# openTPM-v35.net
KiCad netlist of a schematic drawn in EAGLE
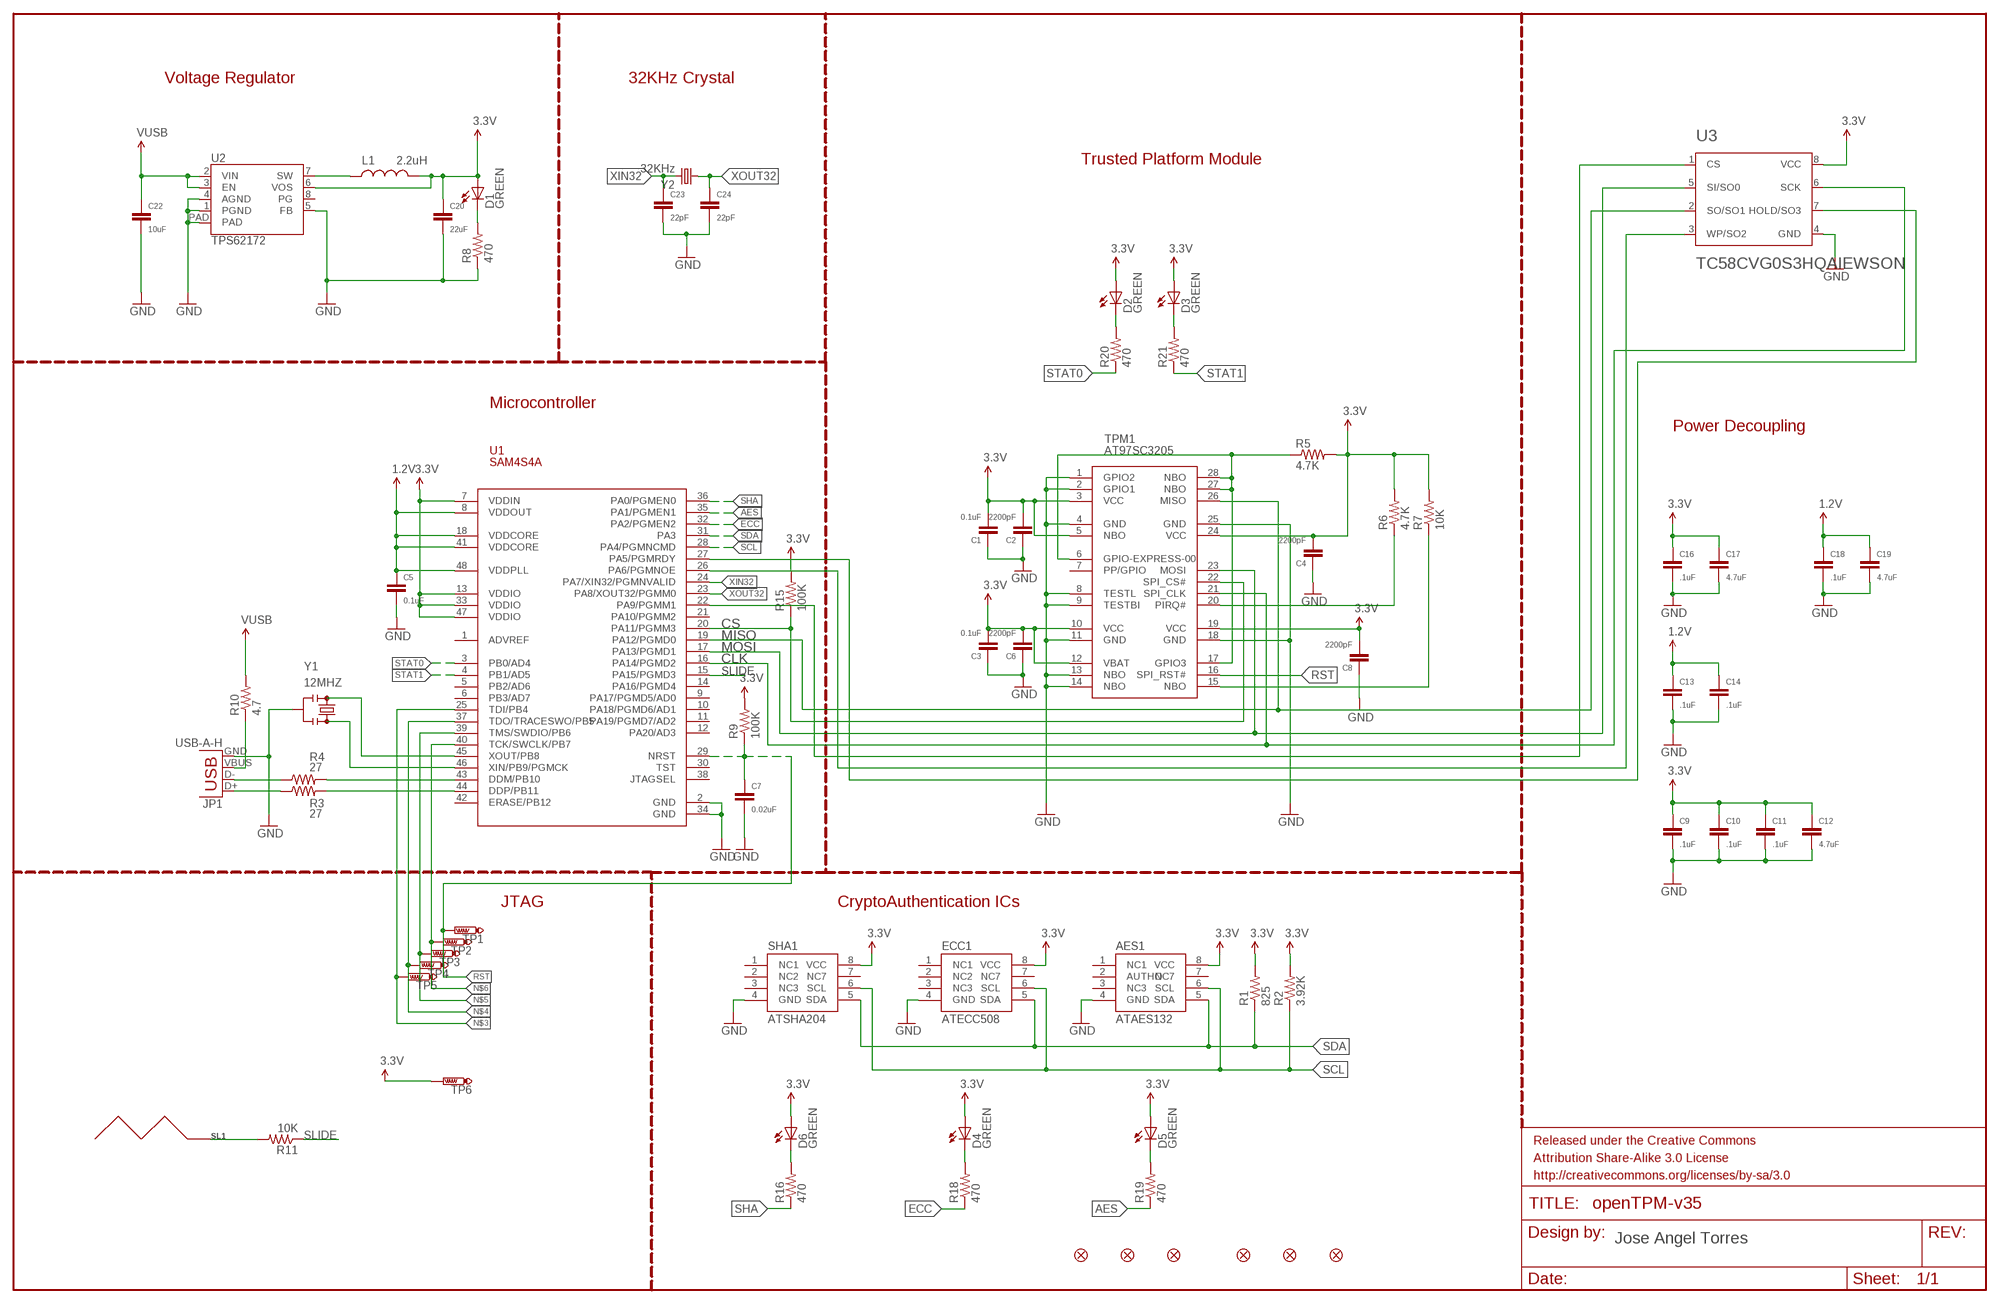
[diagram p0: schematic, sheet 1]

(export (version "E")
  (design (tool "Eeschema 10.0.6"))
  (components
    (comp (ref "AES1")
      (value "ATAES132")
      (footprint "eagle-import:CRYPTOTRONIX_SOIC8")
      (libsource (lib "eagle-import") (part "CRYPTOTRONIX_ATAES132"))
    )
    (comp (ref "C1")
      (value "0.1uF")
      (footprint "eagle-import:0402")
      (libsource (lib "eagle-import") (part "CAPACITOR.0402"))
    )
    (comp (ref "C2")
      (value "2200pF")
      (footprint "eagle-import:0402")
      (libsource (lib "eagle-import") (part "CAPACITOR.0402"))
    )
    (comp (ref "C3")
      (value "0.1uF")
      (footprint "eagle-import:0402")
      (libsource (lib "eagle-import") (part "CAPACITOR.0402"))
    )
    (comp (ref "C4")
      (value "2200pF")
      (footprint "eagle-import:0402")
      (libsource (lib "eagle-import") (part "CAPACITOR.0402"))
    )
    (comp (ref "C5")
      (value "0.1uF")
      (footprint "eagle-import:0402")
      (libsource (lib "eagle-import") (part "CAPACITOR.0402"))
    )
    (comp (ref "C6")
      (value "2200pF")
      (footprint "eagle-import:0402")
      (libsource (lib "eagle-import") (part "CAPACITOR.0402"))
    )
    (comp (ref "C7")
      (value "0.02uF")
      (footprint "eagle-import:0402")
      (libsource (lib "eagle-import") (part "CAPACITOR.0402"))
    )
    (comp (ref "C8")
      (value "2200pF")
      (footprint "eagle-import:0402")
      (libsource (lib "eagle-import") (part "CAPACITOR.0402"))
    )
    (comp (ref "C9")
      (value ".1uF")
      (footprint "eagle-import:0402")
      (libsource (lib "eagle-import") (part "CAPACITOR.0402"))
    )
    (comp (ref "C10")
      (value ".1uF")
      (footprint "eagle-import:0402")
      (libsource (lib "eagle-import") (part "CAPACITOR.0402"))
    )
    (comp (ref "C11")
      (value ".1uF")
      (footprint "eagle-import:0402")
      (libsource (lib "eagle-import") (part "CAPACITOR.0402"))
    )
    (comp (ref "C12")
      (value "4.7uF")
      (footprint "eagle-import:0402")
      (libsource (lib "eagle-import") (part "CAPACITOR.0402"))
    )
    (comp (ref "C13")
      (value ".1uF")
      (footprint "eagle-import:0402")
      (libsource (lib "eagle-import") (part "CAPACITOR.0402"))
    )
    (comp (ref "C14")
      (value ".1uF")
      (footprint "eagle-import:0402")
      (libsource (lib "eagle-import") (part "CAPACITOR.0402"))
    )
    (comp (ref "C16")
      (value ".1uF")
      (footprint "eagle-import:0402")
      (libsource (lib "eagle-import") (part "CAPACITOR.0402"))
    )
    (comp (ref "C17")
      (value "4.7uF")
      (footprint "eagle-import:0402")
      (libsource (lib "eagle-import") (part "CAPACITOR.0402"))
    )
    (comp (ref "C18")
      (value ".1uF")
      (footprint "eagle-import:0402")
      (libsource (lib "eagle-import") (part "CAPACITOR.0402"))
    )
    (comp (ref "C19")
      (value "4.7uF")
      (footprint "eagle-import:0402")
      (libsource (lib "eagle-import") (part "CAPACITOR.0402"))
    )
    (comp (ref "C20")
      (value "22uF")
      (footprint "eagle-import:0603")
      (libsource (lib "eagle-import") (part "CAPACITOR.0603"))
    )
    (comp (ref "C22")
      (value "10uF")
      (footprint "eagle-import:0402")
      (libsource (lib "eagle-import") (part "CAPACITOR.0402"))
    )
    (comp (ref "C23")
      (value "22pF")
      (footprint "eagle-import:0402")
      (libsource (lib "eagle-import") (part "CAPACITOR.0402"))
    )
    (comp (ref "C24")
      (value "22pF")
      (footprint "eagle-import:0402")
      (libsource (lib "eagle-import") (part "CAPACITOR.0402"))
    )
    (comp (ref "D1")
      (value "GREEN")
      (footprint "eagle-import:SPARKFUN-LED_LED-0603")
      (libsource (lib "eagle-import") (part "SPARKFUN-LED_LED-GREEN0603"))
    )
    (comp (ref "D2")
      (value "GREEN")
      (footprint "eagle-import:SPARKFUN-LED_LED-0603")
      (libsource (lib "eagle-import") (part "SPARKFUN-LED_LED-GREEN0603"))
    )
    (comp (ref "D3")
      (value "GREEN")
      (footprint "eagle-import:SPARKFUN-LED_LED-0603")
      (libsource (lib "eagle-import") (part "SPARKFUN-LED_LED-GREEN0603"))
    )
    (comp (ref "D4")
      (value "GREEN")
      (footprint "eagle-import:SPARKFUN-LED_LED-0603")
      (libsource (lib "eagle-import") (part "SPARKFUN-LED_LED-GREEN0603"))
    )
    (comp (ref "D5")
      (value "GREEN")
      (footprint "eagle-import:SPARKFUN-LED_LED-0603")
      (libsource (lib "eagle-import") (part "SPARKFUN-LED_LED-GREEN0603"))
    )
    (comp (ref "D6")
      (value "GREEN")
      (footprint "eagle-import:SPARKFUN-LED_LED-0603")
      (libsource (lib "eagle-import") (part "SPARKFUN-LED_LED-GREEN0603"))
    )
    (comp (ref "ECC1")
      (value "ATECC508")
      (footprint "eagle-import:CRYPTOTRONIX_SOIC8")
      (libsource (lib "eagle-import") (part "ATECC508"))
    )
    (comp (ref "FID1")
      (value "SPARKFUN-AESTHETICS_FIDUCIAL1X2")
      (footprint "eagle-import:SPARKFUN-AESTHETICS_FIDUCIAL-1X2")
      (libsource (lib "eagle-import") (part "SPARKFUN-AESTHETICS_FIDUCIAL1X2"))
    )
    (comp (ref "FID2")
      (value "SPARKFUN-AESTHETICS_FIDUCIAL1X2")
      (footprint "eagle-import:SPARKFUN-AESTHETICS_FIDUCIAL-1X2")
      (libsource (lib "eagle-import") (part "SPARKFUN-AESTHETICS_FIDUCIAL1X2"))
    )
    (comp (ref "FID3")
      (value "SPARKFUN-AESTHETICS_FIDUCIAL1X2")
      (footprint "eagle-import:SPARKFUN-AESTHETICS_FIDUCIAL-1X2")
      (libsource (lib "eagle-import") (part "SPARKFUN-AESTHETICS_FIDUCIAL1X2"))
    )
    (comp (ref "FID4")
      (value "SPARKFUN-AESTHETICS_FIDUCIAL1X2")
      (footprint "eagle-import:SPARKFUN-AESTHETICS_FIDUCIAL-1X2")
      (libsource (lib "eagle-import") (part "SPARKFUN-AESTHETICS_FIDUCIAL1X2"))
    )
    (comp (ref "FID5")
      (value "SPARKFUN-AESTHETICS_FIDUCIAL1X2")
      (footprint "eagle-import:SPARKFUN-AESTHETICS_FIDUCIAL-1X2")
      (libsource (lib "eagle-import") (part "SPARKFUN-AESTHETICS_FIDUCIAL1X2"))
    )
    (comp (ref "FID6")
      (value "SPARKFUN-AESTHETICS_FIDUCIAL1X2")
      (footprint "eagle-import:SPARKFUN-AESTHETICS_FIDUCIAL-1X2")
      (libsource (lib "eagle-import") (part "SPARKFUN-AESTHETICS_FIDUCIAL1X2"))
    )
    (comp (ref "JP1")
      (value "USB-A-H")
      (footprint "eagle-import:USB-A-H")
      (libsource (lib "eagle-import") (part "USB-A-H"))
    )
    (comp (ref "L1")
      (value "2.2uH")
      (footprint "eagle-import:C0402")
      (libsource (lib "eagle-import") (part "INDUCTOR0402"))
    )
    (comp (ref "R1")
      (value "825")
      (footprint "eagle-import:0402")
      (libsource (lib "eagle-import") (part "RESISTOR.0402"))
    )
    (comp (ref "R2")
      (value "3.92K")
      (footprint "eagle-import:0402")
      (libsource (lib "eagle-import") (part "RESISTOR.0402"))
    )
    (comp (ref "R3")
      (value "27")
      (footprint "eagle-import:0402")
      (libsource (lib "eagle-import") (part "RESISTOR.0402"))
    )
    (comp (ref "R4")
      (value "27")
      (footprint "eagle-import:0402")
      (libsource (lib "eagle-import") (part "RESISTOR.0402"))
    )
    (comp (ref "R5")
      (value "4.7K")
      (footprint "eagle-import:0402")
      (libsource (lib "eagle-import") (part "RESISTOR.0402"))
    )
    (comp (ref "R6")
      (value "4.7K")
      (footprint "eagle-import:0402")
      (libsource (lib "eagle-import") (part "RESISTOR.0402"))
    )
    (comp (ref "R7")
      (value "10K")
      (footprint "eagle-import:0402")
      (libsource (lib "eagle-import") (part "RESISTOR.0402"))
    )
    (comp (ref "R8")
      (value "470")
      (footprint "eagle-import:0402")
      (libsource (lib "eagle-import") (part "RESISTOR.0402"))
    )
    (comp (ref "R9")
      (value "100K")
      (footprint "eagle-import:0402")
      (libsource (lib "eagle-import") (part "RESISTOR.0402"))
    )
    (comp (ref "R10")
      (value "4.7")
      (footprint "eagle-import:0402")
      (libsource (lib "eagle-import") (part "RESISTOR.0402"))
    )
    (comp (ref "R11")
      (value "10K")
      (footprint "eagle-import:0402")
      (libsource (lib "eagle-import") (part "RESISTOR.0402"))
    )
    (comp (ref "R15")
      (value "100K")
      (footprint "eagle-import:0402")
      (libsource (lib "eagle-import") (part "RESISTOR.0402"))
    )
    (comp (ref "R16")
      (value "470")
      (footprint "eagle-import:0402")
      (libsource (lib "eagle-import") (part "RESISTOR.0402"))
    )
    (comp (ref "R18")
      (value "470")
      (footprint "eagle-import:0402")
      (libsource (lib "eagle-import") (part "RESISTOR.0402"))
    )
    (comp (ref "R19")
      (value "470")
      (footprint "eagle-import:0402")
      (libsource (lib "eagle-import") (part "RESISTOR.0402"))
    )
    (comp (ref "R20")
      (value "470")
      (footprint "eagle-import:0402")
      (libsource (lib "eagle-import") (part "RESISTOR.0402"))
    )
    (comp (ref "R21")
      (value "470")
      (footprint "eagle-import:0402")
      (libsource (lib "eagle-import") (part "RESISTOR.0402"))
    )
    (comp (ref "SHA1")
      (value "ATSHA204")
      (footprint "eagle-import:CRYPTOTRONIX_SOIC8")
      (libsource (lib "eagle-import") (part "CRYPTOTRONIX_ATSHA204"))
    )
    (comp (ref "SL1")
      (value "SLIDER_PASSIVE_1SEG")
      (footprint "eagle-import:SLIDER_PASSIVE_1SEG_12MM")
      (libsource (lib "eagle-import") (part "SLIDER_PASSIVE_1SEG"))
    )
    (comp (ref "TP1")
      (value "PTR1B1,27")
      (footprint "eagle-import:B1,27")
      (libsource (lib "eagle-import") (part "PTR1B1,27"))
    )
    (comp (ref "TP2")
      (value "PTR1B1,27")
      (footprint "eagle-import:B1,27")
      (libsource (lib "eagle-import") (part "PTR1B1,27"))
    )
    (comp (ref "TP3")
      (value "PTR1B1,27")
      (footprint "eagle-import:B1,27")
      (libsource (lib "eagle-import") (part "PTR1B1,27"))
    )
    (comp (ref "TP4")
      (value "PTR1B1,27")
      (footprint "eagle-import:B1,27")
      (libsource (lib "eagle-import") (part "PTR1B1,27"))
    )
    (comp (ref "TP5")
      (value "PTR1B1,27")
      (footprint "eagle-import:B1,27")
      (libsource (lib "eagle-import") (part "PTR1B1,27"))
    )
    (comp (ref "TP6")
      (value "PTR1B1,27")
      (footprint "eagle-import:B1,27")
      (libsource (lib "eagle-import") (part "PTR1B1,27"))
    )
    (comp (ref "TPM1")
      (value "AT97SC3205")
      (footprint "eagle-import:TSSOP28")
      (libsource (lib "eagle-import") (part "AT97SC3205"))
    )
    (comp (ref "U1")
      (value "SAM4S4A")
      (footprint "eagle-import:LQFP-48")
      (libsource (lib "eagle-import") (part "SAM4S4A"))
    )
    (comp (ref "U2")
      (value "TPS62172")
      (footprint "eagle-import:WSON-8-PAD")
      (libsource (lib "eagle-import") (part "TPS62172"))
    )
    (comp (ref "U3")
      (value "TC58CVG0S3HQAIEWSON")
      (footprint "eagle-import:WSON-8-PAD")
      (libsource (lib "eagle-import") (part "TC58CVG0S3HQAIEWSON"))
    )
    (comp (ref "Y1")
      (value "12MHZ")
      (footprint "eagle-import:RESONATOR-SMD")
      (libsource (lib "eagle-import") (part "RESONATOR12MHZ"))
    )
    (comp (ref "Y2")
      (value "32KHz")
      (footprint "eagle-import:CRYSTAL-32KHZ-SMD_EPSON_MC146")
      (libsource (lib "eagle-import") (part "CRYSTALEPSONMC146"))
    )
  )
  (nets
    (net (code "1") (name "/CLK") (class "Default")
      (node (ref "TPM1") (pin "21") (pinfunction "SPI_CLK_21") (pintype "bidirectional"))
      (node (ref "U1") (pin "16") (pinfunction "PA14/PGMD2_16") (pintype "bidirectional"))
      (node (ref "U3") (pin "6") (pinfunction "SCK_6") (pintype "bidirectional"))
    )
    (net (code "2") (name "/CS") (class "Default")
      (node (ref "R15") (pin "1") (pinfunction "1_1") (pintype "passive"))
      (node (ref "TPM1") (pin "22") (pinfunction "SPI_CS#_22") (pintype "power_in"))
      (node (ref "U1") (pin "20") (pinfunction "PA11/PGMM3_20") (pintype "bidirectional"))
    )
    (net (code "3") (name "/MISO") (class "Default")
      (node (ref "TPM1") (pin "26") (pinfunction "MISO_26") (pintype "power_in"))
      (node (ref "U1") (pin "19") (pinfunction "PA12/PGMD0_19") (pintype "bidirectional"))
      (node (ref "U3") (pin "2") (pinfunction "SO/SO1_2") (pintype "bidirectional"))
    )
    (net (code "4") (name "/MOSI") (class "Default")
      (node (ref "TPM1") (pin "23") (pinfunction "MOSI_23") (pintype "power_in"))
      (node (ref "U1") (pin "17") (pinfunction "PA13/PGMD1_17") (pintype "bidirectional"))
      (node (ref "U3") (pin "5") (pinfunction "SI/SO0_5") (pintype "bidirectional"))
    )
    (net (code "5") (name "/SLIDE") (class "Default")
      (node (ref "R11") (pin "1") (pinfunction "1_1") (pintype "passive"))
      (node (ref "U1") (pin "15") (pinfunction "PA15/PGMD3_15") (pintype "bidirectional"))
    )
    (net (code "6") (name "1.2V") (class "Default")
      (node (ref "C13") (pin "1") (pinfunction "1_1") (pintype "passive"))
      (node (ref "C14") (pin "1") (pinfunction "1_1") (pintype "passive"))
      (node (ref "C18") (pin "1") (pinfunction "1_1") (pintype "passive"))
      (node (ref "C19") (pin "1") (pinfunction "1_1") (pintype "passive"))
      (node (ref "C5") (pin "1") (pinfunction "1_1") (pintype "passive"))
      (node (ref "U1") (pin "18") (pinfunction "VDDCORE_18") (pintype "bidirectional"))
      (node (ref "U1") (pin "41") (pinfunction "VDDCORE_41") (pintype "bidirectional"))
      (node (ref "U1") (pin "48") (pinfunction "VDDPLL_48") (pintype "bidirectional"))
      (node (ref "U1") (pin "8") (pinfunction "VDDOUT_8") (pintype "bidirectional"))
    )
    (net (code "7") (name "3.3V") (class "Default")
      (node (ref "AES1") (pin "8") (pinfunction "VCC_8") (pintype "power_in"))
      (node (ref "C1") (pin "2") (pinfunction "2_2") (pintype "passive"))
      (node (ref "C10") (pin "1") (pinfunction "1_1") (pintype "passive"))
      (node (ref "C11") (pin "1") (pinfunction "1_1") (pintype "passive"))
      (node (ref "C12") (pin "1") (pinfunction "1_1") (pintype "passive"))
      (node (ref "C16") (pin "1") (pinfunction "1_1") (pintype "passive"))
      (node (ref "C17") (pin "1") (pinfunction "1_1") (pintype "passive"))
      (node (ref "C2") (pin "2") (pinfunction "2_2") (pintype "passive"))
      (node (ref "C20") (pin "1") (pinfunction "1_1") (pintype "passive"))
      (node (ref "C3") (pin "2") (pinfunction "2_2") (pintype "passive"))
      (node (ref "C4") (pin "2") (pinfunction "2_2") (pintype "passive"))
      (node (ref "C6") (pin "2") (pinfunction "2_2") (pintype "passive"))
      (node (ref "C8") (pin "2") (pinfunction "2_2") (pintype "passive"))
      (node (ref "C9") (pin "1") (pinfunction "1_1") (pintype "passive"))
      (node (ref "D1") (pin "A") (pinfunction "A_A") (pintype "passive"))
      (node (ref "D2") (pin "A") (pinfunction "A_A") (pintype "passive"))
      (node (ref "D3") (pin "A") (pinfunction "A_A") (pintype "passive"))
      (node (ref "D4") (pin "A") (pinfunction "A_A") (pintype "passive"))
      (node (ref "D5") (pin "A") (pinfunction "A_A") (pintype "passive"))
      (node (ref "D6") (pin "A") (pinfunction "A_A") (pintype "passive"))
      (node (ref "ECC1") (pin "8") (pinfunction "VCC_8") (pintype "power_in"))
      (node (ref "L1") (pin "2") (pinfunction "2_2") (pintype "passive"))
      (node (ref "R1") (pin "2") (pinfunction "2_2") (pintype "passive"))
      (node (ref "R15") (pin "2") (pinfunction "2_2") (pintype "passive"))
      (node (ref "R2") (pin "2") (pinfunction "2_2") (pintype "passive"))
      (node (ref "R5") (pin "2") (pinfunction "2_2") (pintype "passive"))
      (node (ref "R6") (pin "2") (pinfunction "2_2") (pintype "passive"))
      (node (ref "R7") (pin "2") (pinfunction "2_2") (pintype "passive"))
      (node (ref "R9") (pin "2") (pinfunction "2_2") (pintype "passive"))
      (node (ref "SHA1") (pin "8") (pinfunction "VCC_8") (pintype "power_in"))
      (node (ref "TP6") (pin "TP") (pinfunction "TP_TP") (pintype "input"))
      (node (ref "TPM1") (pin "10") (pinfunction "VCC_10") (pintype "power_in"))
      (node (ref "TPM1") (pin "12") (pinfunction "VBAT_12") (pintype "bidirectional"))
      (node (ref "TPM1") (pin "19") (pinfunction "VCC_19") (pintype "power_in"))
      (node (ref "TPM1") (pin "24") (pinfunction "VCC_24") (pintype "power_in"))
      (node (ref "TPM1") (pin "3") (pinfunction "VCC_3") (pintype "power_in"))
      (node (ref "TPM1") (pin "5") (pinfunction "NBO_5") (pintype "bidirectional"))
      (node (ref "U1") (pin "13") (pinfunction "VDDIO_13") (pintype "bidirectional"))
      (node (ref "U1") (pin "33") (pinfunction "VDDIO_33") (pintype "bidirectional"))
      (node (ref "U1") (pin "47") (pinfunction "VDDIO_47") (pintype "bidirectional"))
      (node (ref "U1") (pin "7") (pinfunction "VDDIN_7") (pintype "bidirectional"))
      (node (ref "U2") (pin "6") (pinfunction "VOS_6") (pintype "bidirectional"))
      (node (ref "U3") (pin "8") (pinfunction "VCC_8") (pintype "bidirectional"))
    )
    (net (code "8") (name "AES") (class "Default")
      (node (ref "R19") (pin "1") (pinfunction "1_1") (pintype "passive"))
      (node (ref "U1") (pin "35") (pinfunction "PA1/PGMEN1_35") (pintype "bidirectional"))
    )
    (net (code "9") (name "ECC") (class "Default")
      (node (ref "R18") (pin "1") (pinfunction "1_1") (pintype "passive"))
      (node (ref "U1") (pin "32") (pinfunction "PA2/PGMEN2_32") (pintype "bidirectional"))
    )
    (net (code "10") (name "GND") (class "Default")
      (node (ref "AES1") (pin "4") (pinfunction "GND_4") (pintype "power_in"))
      (node (ref "C1") (pin "1") (pinfunction "1_1") (pintype "passive"))
      (node (ref "C10") (pin "2") (pinfunction "2_2") (pintype "passive"))
      (node (ref "C11") (pin "2") (pinfunction "2_2") (pintype "passive"))
      (node (ref "C12") (pin "2") (pinfunction "2_2") (pintype "passive"))
      (node (ref "C13") (pin "2") (pinfunction "2_2") (pintype "passive"))
      (node (ref "C14") (pin "2") (pinfunction "2_2") (pintype "passive"))
      (node (ref "C16") (pin "2") (pinfunction "2_2") (pintype "passive"))
      (node (ref "C17") (pin "2") (pinfunction "2_2") (pintype "passive"))
      (node (ref "C18") (pin "2") (pinfunction "2_2") (pintype "passive"))
      (node (ref "C19") (pin "2") (pinfunction "2_2") (pintype "passive"))
      (node (ref "C2") (pin "1") (pinfunction "1_1") (pintype "passive"))
      (node (ref "C20") (pin "2") (pinfunction "2_2") (pintype "passive"))
      (node (ref "C22") (pin "2") (pinfunction "2_2") (pintype "passive"))
      (node (ref "C23") (pin "2") (pinfunction "2_2") (pintype "passive"))
      (node (ref "C24") (pin "2") (pinfunction "2_2") (pintype "passive"))
      (node (ref "C3") (pin "1") (pinfunction "1_1") (pintype "passive"))
      (node (ref "C4") (pin "1") (pinfunction "1_1") (pintype "passive"))
      (node (ref "C5") (pin "2") (pinfunction "2_2") (pintype "passive"))
      (node (ref "C6") (pin "1") (pinfunction "1_1") (pintype "passive"))
      (node (ref "C7") (pin "2") (pinfunction "2_2") (pintype "passive"))
      (node (ref "C8") (pin "1") (pinfunction "1_1") (pintype "passive"))
      (node (ref "C9") (pin "2") (pinfunction "2_2") (pintype "passive"))
      (node (ref "ECC1") (pin "4") (pinfunction "GND_4") (pintype "power_in"))
      (node (ref "JP1") (pin "GND") (pinfunction "GND_GND") (pintype "bidirectional"))
      (node (ref "R8") (pin "1") (pinfunction "1_1") (pintype "passive"))
      (node (ref "SHA1") (pin "4") (pinfunction "GND_4") (pintype "power_in"))
      (node (ref "TPM1") (pin "1") (pinfunction "GPIO2_1") (pintype "bidirectional"))
      (node (ref "TPM1") (pin "11") (pinfunction "GND_11") (pintype "power_in"))
      (node (ref "TPM1") (pin "13") (pinfunction "NBO_13") (pintype "bidirectional"))
      (node (ref "TPM1") (pin "14") (pinfunction "NBO_14") (pintype "bidirectional"))
      (node (ref "TPM1") (pin "18") (pinfunction "GND_18") (pintype "power_in"))
      (node (ref "TPM1") (pin "2") (pinfunction "GPIO1_2") (pintype "bidirectional"))
      (node (ref "TPM1") (pin "25") (pinfunction "GND_25") (pintype "power_in"))
      (node (ref "TPM1") (pin "4") (pinfunction "GND_4") (pintype "power_in"))
      (node (ref "TPM1") (pin "8") (pinfunction "TESTL_8") (pintype "bidirectional"))
      (node (ref "TPM1") (pin "9") (pinfunction "TESTBI_9") (pintype "bidirectional"))
      (node (ref "U1") (pin "2") (pinfunction "GND_2") (pintype "bidirectional"))
      (node (ref "U1") (pin "34") (pinfunction "GND_34") (pintype "bidirectional"))
      (node (ref "U2") (pin "1") (pinfunction "PGND_1") (pintype "bidirectional"))
      (node (ref "U2") (pin "4") (pinfunction "AGND_4") (pintype "bidirectional"))
      (node (ref "U2") (pin "5") (pinfunction "FB_5") (pintype "bidirectional"))
      (node (ref "U2") (pin "PAD") (pinfunction "PAD_PAD") (pintype "bidirectional"))
      (node (ref "U3") (pin "4") (pinfunction "GND_4") (pintype "bidirectional"))
      (node (ref "Y1") (pin "2") (pinfunction "2_2") (pintype "passive"))
    )
    (net (code "11") (name "N$3") (class "Default")
      (node (ref "TP5") (pin "TP") (pinfunction "TP_TP") (pintype "input"))
      (node (ref "U1") (pin "25") (pinfunction "TDI/PB4_25") (pintype "bidirectional"))
    )
    (net (code "12") (name "N$4") (class "Default")
      (node (ref "TP4") (pin "TP") (pinfunction "TP_TP") (pintype "input"))
      (node (ref "U1") (pin "37") (pinfunction "TDO/TRACESWO/PB5_37") (pintype "bidirectional"))
    )
    (net (code "13") (name "N$5") (class "Default")
      (node (ref "TP3") (pin "TP") (pinfunction "TP_TP") (pintype "input"))
      (node (ref "U1") (pin "39") (pinfunction "TMS/SWDIO/PB6_39") (pintype "bidirectional"))
    )
    (net (code "14") (name "N$6") (class "Default")
      (node (ref "TP2") (pin "TP") (pinfunction "TP_TP") (pintype "input"))
      (node (ref "U1") (pin "40") (pinfunction "TCK/SWCLK/PB7_40") (pintype "bidirectional"))
    )
    (net (code "15") (name "Net-(D1-PadC)") (class "Default")
      (node (ref "D1") (pin "C") (pinfunction "C_C") (pintype "passive"))
      (node (ref "R8") (pin "2") (pinfunction "2_2") (pintype "passive"))
    )
    (net (code "16") (name "Net-(D2-PadC)") (class "Default")
      (node (ref "D2") (pin "C") (pinfunction "C_C") (pintype "passive"))
      (node (ref "R20") (pin "2") (pinfunction "2_2") (pintype "passive"))
    )
    (net (code "17") (name "Net-(D3-PadC)") (class "Default")
      (node (ref "D3") (pin "C") (pinfunction "C_C") (pintype "passive"))
      (node (ref "R21") (pin "2") (pinfunction "2_2") (pintype "passive"))
    )
    (net (code "18") (name "Net-(D4-PadC)") (class "Default")
      (node (ref "D4") (pin "C") (pinfunction "C_C") (pintype "passive"))
      (node (ref "R18") (pin "2") (pinfunction "2_2") (pintype "passive"))
    )
    (net (code "19") (name "Net-(D5-PadC)") (class "Default")
      (node (ref "D5") (pin "C") (pinfunction "C_C") (pintype "passive"))
      (node (ref "R19") (pin "2") (pinfunction "2_2") (pintype "passive"))
    )
    (net (code "20") (name "Net-(D6-PadC)") (class "Default")
      (node (ref "D6") (pin "C") (pinfunction "C_C") (pintype "passive"))
      (node (ref "R16") (pin "2") (pinfunction "2_2") (pintype "passive"))
    )
    (net (code "21") (name "Net-(JP1-PadD+)") (class "Default")
      (node (ref "JP1") (pin "D+") (pinfunction "D+_D+") (pintype "bidirectional"))
      (node (ref "R3") (pin "1") (pinfunction "1_1") (pintype "passive"))
    )
    (net (code "22") (name "Net-(JP1-PadD-)") (class "Default")
      (node (ref "JP1") (pin "D-") (pinfunction "D-_D-") (pintype "bidirectional"))
      (node (ref "R4") (pin "1") (pinfunction "1_1") (pintype "passive"))
    )
    (net (code "23") (name "Net-(JP1-PadVBUS)") (class "Default")
      (node (ref "JP1") (pin "VBUS") (pinfunction "VBUS_VBUS") (pintype "bidirectional"))
      (node (ref "R10") (pin "1") (pinfunction "1_1") (pintype "passive"))
    )
    (net (code "24") (name "Net-(R7-Pad1)") (class "Default")
      (node (ref "R7") (pin "1") (pinfunction "1_1") (pintype "passive"))
      (node (ref "TPM1") (pin "15") (pinfunction "NBO_15") (pintype "bidirectional"))
    )
    (net (code "25") (name "Net-(SL1-SL1)") (class "Default")
      (node (ref "R11") (pin "2") (pinfunction "2_2") (pintype "passive"))
      (node (ref "SL1") (pin "S1") (pinfunction "SL1_S1") (pintype "passive"))
    )
    (net (code "26") (name "Net-(TPM1-GPIO-EXPRESS-00)") (class "Default")
      (node (ref "R5") (pin "1") (pinfunction "1_1") (pintype "passive"))
      (node (ref "TPM1") (pin "17") (pinfunction "GPIO3_17") (pintype "power_in"))
      (node (ref "TPM1") (pin "27") (pinfunction "NBO_27") (pintype "bidirectional"))
      (node (ref "TPM1") (pin "28") (pinfunction "NBO_28") (pintype "bidirectional"))
      (node (ref "TPM1") (pin "6") (pinfunction "GPIO-EXPRESS-00_6") (pintype "power_in"))
    )
    (net (code "27") (name "Net-(TPM1-PIRQ#)") (class "Default")
      (node (ref "R6") (pin "1") (pinfunction "1_1") (pintype "passive"))
      (node (ref "TPM1") (pin "20") (pinfunction "PIRQ#_20") (pintype "power_in"))
    )
    (net (code "28") (name "Net-(U1-DDM{slash}PB10)") (class "Default")
      (node (ref "R4") (pin "2") (pinfunction "2_2") (pintype "passive"))
      (node (ref "U1") (pin "43") (pinfunction "DDM/PB10_43") (pintype "bidirectional"))
    )
    (net (code "29") (name "Net-(U1-DDP{slash}PB11)") (class "Default")
      (node (ref "R3") (pin "2") (pinfunction "2_2") (pintype "passive"))
      (node (ref "U1") (pin "44") (pinfunction "DDP/PB11_44") (pintype "bidirectional"))
    )
    (net (code "30") (name "Net-(U1-PA5{slash}PGMRDY)") (class "Default")
      (node (ref "U1") (pin "27") (pinfunction "PA5/PGMRDY_27") (pintype "bidirectional"))
      (node (ref "U3") (pin "7") (pinfunction "HOLD/SO3_7") (pintype "bidirectional"))
    )
    (net (code "31") (name "Net-(U1-PA6{slash}PGMNOE)") (class "Default")
      (node (ref "U1") (pin "26") (pinfunction "PA6/PGMNOE_26") (pintype "bidirectional"))
      (node (ref "U3") (pin "3") (pinfunction "WP/SO2_3") (pintype "bidirectional"))
    )
    (net (code "32") (name "Net-(U1-PA9{slash}PGMM1)") (class "Default")
      (node (ref "U1") (pin "22") (pinfunction "PA9/PGMM1_22") (pintype "bidirectional"))
      (node (ref "U3") (pin "1") (pinfunction "CS_1") (pintype "bidirectional"))
    )
    (net (code "33") (name "Net-(U1-XIN{slash}PB9{slash}PGMCK)") (class "Default")
      (node (ref "U1") (pin "46") (pinfunction "XIN/PB9/PGMCK_46") (pintype "bidirectional"))
      (node (ref "Y1") (pin "3") (pinfunction "3_3") (pintype "passive"))
    )
    (net (code "34") (name "Net-(U1-XOUT{slash}PB8)") (class "Default")
      (node (ref "U1") (pin "45") (pinfunction "XOUT/PB8_45") (pintype "bidirectional"))
      (node (ref "Y1") (pin "1") (pinfunction "1_1") (pintype "passive"))
    )
    (net (code "35") (name "Net-(U2-SW)") (class "Default")
      (node (ref "L1") (pin "1") (pinfunction "1_1") (pintype "passive"))
      (node (ref "U2") (pin "7") (pinfunction "SW_7") (pintype "bidirectional"))
    )
    (net (code "36") (name "RST") (class "Default")
      (node (ref "C7") (pin "1") (pinfunction "1_1") (pintype "passive"))
      (node (ref "R9") (pin "1") (pinfunction "1_1") (pintype "passive"))
      (node (ref "TP1") (pin "TP") (pinfunction "TP_TP") (pintype "input"))
      (node (ref "TPM1") (pin "16") (pinfunction "SPI_RST#_16") (pintype "bidirectional"))
      (node (ref "U1") (pin "29") (pinfunction "NRST_29") (pintype "bidirectional"))
    )
    (net (code "37") (name "SCL") (class "Default")
      (node (ref "AES1") (pin "6") (pinfunction "SCL_6") (pintype "bidirectional"))
      (node (ref "ECC1") (pin "6") (pinfunction "SCL_6") (pintype "bidirectional"))
      (node (ref "R2") (pin "1") (pinfunction "1_1") (pintype "passive"))
      (node (ref "SHA1") (pin "6") (pinfunction "SCL_6") (pintype "bidirectional"))
      (node (ref "U1") (pin "28") (pinfunction "PA4/PGMNCMD_28") (pintype "bidirectional"))
    )
    (net (code "38") (name "SDA") (class "Default")
      (node (ref "AES1") (pin "5") (pinfunction "SDA_5") (pintype "bidirectional"))
      (node (ref "ECC1") (pin "5") (pinfunction "SDA_5") (pintype "bidirectional"))
      (node (ref "R1") (pin "1") (pinfunction "1_1") (pintype "passive"))
      (node (ref "SHA1") (pin "5") (pinfunction "SDA_5") (pintype "bidirectional"))
      (node (ref "U1") (pin "31") (pinfunction "PA3_31") (pintype "bidirectional"))
    )
    (net (code "39") (name "SHA") (class "Default")
      (node (ref "R16") (pin "1") (pinfunction "1_1") (pintype "passive"))
      (node (ref "U1") (pin "36") (pinfunction "PA0/PGMEN0_36") (pintype "bidirectional"))
    )
    (net (code "40") (name "STAT0") (class "Default")
      (node (ref "R20") (pin "1") (pinfunction "1_1") (pintype "passive"))
      (node (ref "U1") (pin "3") (pinfunction "PB0/AD4_3") (pintype "bidirectional"))
    )
    (net (code "41") (name "STAT1") (class "Default")
      (node (ref "R21") (pin "1") (pinfunction "1_1") (pintype "passive"))
      (node (ref "U1") (pin "4") (pinfunction "PB1/AD5_4") (pintype "bidirectional"))
    )
    (net (code "42") (name "VUSB") (class "Default")
      (node (ref "C22") (pin "1") (pinfunction "1_1") (pintype "passive"))
      (node (ref "R10") (pin "2") (pinfunction "2_2") (pintype "passive"))
      (node (ref "U2") (pin "2") (pinfunction "VIN_2") (pintype "bidirectional"))
      (node (ref "U2") (pin "3") (pinfunction "EN_3") (pintype "bidirectional"))
    )
    (net (code "43") (name "XIN32") (class "Default")
      (node (ref "C23") (pin "1") (pinfunction "1_1") (pintype "passive"))
      (node (ref "U1") (pin "24") (pinfunction "PA7/XIN32/PGMNVALID_24") (pintype "bidirectional"))
      (node (ref "Y2") (pin "P$1") (pinfunction "2_P$1") (pintype "passive"))
    )
    (net (code "44") (name "XOUT32") (class "Default")
      (node (ref "C24") (pin "1") (pinfunction "1_1") (pintype "passive"))
      (node (ref "U1") (pin "23") (pinfunction "PA8/XOUT32/PGMM0_23") (pintype "bidirectional"))
      (node (ref "Y2") (pin "P$2") (pinfunction "1_P$2") (pintype "passive"))
    )
    (net (code "45") (name "unconnected-(AES1-AUTHO-Pad2)") (class "Default")
      (node (ref "AES1") (pin "2") (pinfunction "AUTHO_2") (pintype "bidirectional"))
    )
    (net (code "46") (name "unconnected-(AES1-NC1-Pad1)") (class "Default")
      (node (ref "AES1") (pin "1") (pinfunction "NC1_1") (pintype "no_connect"))
    )
    (net (code "47") (name "unconnected-(AES1-NC3-Pad3)") (class "Default")
      (node (ref "AES1") (pin "3") (pinfunction "NC3_3") (pintype "no_connect"))
    )
    (net (code "48") (name "unconnected-(AES1-NC7-Pad7)") (class "Default")
      (node (ref "AES1") (pin "7") (pinfunction "NC7_7") (pintype "no_connect"))
    )
    (net (code "49") (name "unconnected-(ECC1-NC1-Pad1)") (class "Default")
      (node (ref "ECC1") (pin "1") (pinfunction "NC1_1") (pintype "bidirectional"))
    )
    (net (code "50") (name "unconnected-(ECC1-NC2-Pad2)") (class "Default")
      (node (ref "ECC1") (pin "2") (pinfunction "NC2_2") (pintype "no_connect"))
    )
    (net (code "51") (name "unconnected-(ECC1-NC3-Pad3)") (class "Default")
      (node (ref "ECC1") (pin "3") (pinfunction "NC3_3") (pintype "no_connect"))
    )
    (net (code "52") (name "unconnected-(ECC1-NC7-Pad7)") (class "Default")
      (node (ref "ECC1") (pin "7") (pinfunction "NC7_7") (pintype "no_connect"))
    )
    (net (code "53") (name "unconnected-(SHA1-NC1-Pad1)") (class "Default")
      (node (ref "SHA1") (pin "1") (pinfunction "NC1_1") (pintype "no_connect"))
    )
    (net (code "54") (name "unconnected-(SHA1-NC2-Pad2)") (class "Default")
      (node (ref "SHA1") (pin "2") (pinfunction "NC2_2") (pintype "no_connect"))
    )
    (net (code "55") (name "unconnected-(SHA1-NC3-Pad3)") (class "Default")
      (node (ref "SHA1") (pin "3") (pinfunction "NC3_3") (pintype "no_connect"))
    )
    (net (code "56") (name "unconnected-(SHA1-NC7-Pad7)") (class "Default")
      (node (ref "SHA1") (pin "7") (pinfunction "NC7_7") (pintype "no_connect"))
    )
    (net (code "57") (name "unconnected-(TPM1-PP{slash}GPIO-Pad7)") (class "Default")
      (node (ref "TPM1") (pin "7") (pinfunction "PP/GPIO_7") (pintype "bidirectional"))
    )
    (net (code "58") (name "unconnected-(U1-ADVREF-Pad1)") (class "Default")
      (node (ref "U1") (pin "1") (pinfunction "ADVREF_1") (pintype "bidirectional"))
    )
    (net (code "59") (name "unconnected-(U1-ERASE{slash}PB12-Pad42)") (class "Default")
      (node (ref "U1") (pin "42") (pinfunction "ERASE/PB12_42") (pintype "bidirectional"))
    )
    (net (code "60") (name "unconnected-(U1-JTAGSEL-Pad38)") (class "Default")
      (node (ref "U1") (pin "38") (pinfunction "JTAGSEL_38") (pintype "bidirectional"))
    )
    (net (code "61") (name "unconnected-(U1-PA10{slash}PGMM2-Pad21)") (class "Default")
      (node (ref "U1") (pin "21") (pinfunction "PA10/PGMM2_21") (pintype "bidirectional"))
    )
    (net (code "62") (name "unconnected-(U1-PA16{slash}PGMD4-Pad14)") (class "Default")
      (node (ref "U1") (pin "14") (pinfunction "PA16/PGMD4_14") (pintype "bidirectional"))
    )
    (net (code "63") (name "unconnected-(U1-PA17{slash}PGMD5{slash}AD0-Pad9)") (class "Default")
      (node (ref "U1") (pin "9") (pinfunction "PA17/PGMD5/AD0_9") (pintype "bidirectional"))
    )
    (net (code "64") (name "unconnected-(U1-PA18{slash}PGMD6{slash}AD1-Pad10)") (class "Default")
      (node (ref "U1") (pin "10") (pinfunction "PA18/PGMD6/AD1_10") (pintype "bidirectional"))
    )
    (net (code "65") (name "unconnected-(U1-PA19{slash}PGMD7{slash}AD2-Pad11)") (class "Default")
      (node (ref "U1") (pin "11") (pinfunction "PA19/PGMD7/AD2_11") (pintype "bidirectional"))
    )
    (net (code "66") (name "unconnected-(U1-PA20{slash}AD3-Pad12)") (class "Default")
      (node (ref "U1") (pin "12") (pinfunction "PA20/AD3_12") (pintype "bidirectional"))
    )
    (net (code "67") (name "unconnected-(U1-PB2{slash}AD6-Pad5)") (class "Default")
      (node (ref "U1") (pin "5") (pinfunction "PB2/AD6_5") (pintype "bidirectional"))
    )
    (net (code "68") (name "unconnected-(U1-PB3{slash}AD7-Pad6)") (class "Default")
      (node (ref "U1") (pin "6") (pinfunction "PB3/AD7_6") (pintype "bidirectional"))
    )
    (net (code "69") (name "unconnected-(U1-TST-Pad30)") (class "Default")
      (node (ref "U1") (pin "30") (pinfunction "TST_30") (pintype "bidirectional"))
    )
    (net (code "70") (name "unconnected-(U2-PG-Pad8)") (class "Default")
      (node (ref "U2") (pin "8") (pinfunction "PG_8") (pintype "bidirectional"))
    )
  )
)
